# Main.net
KiCad netlist of a schematic drawn in Altium Designer
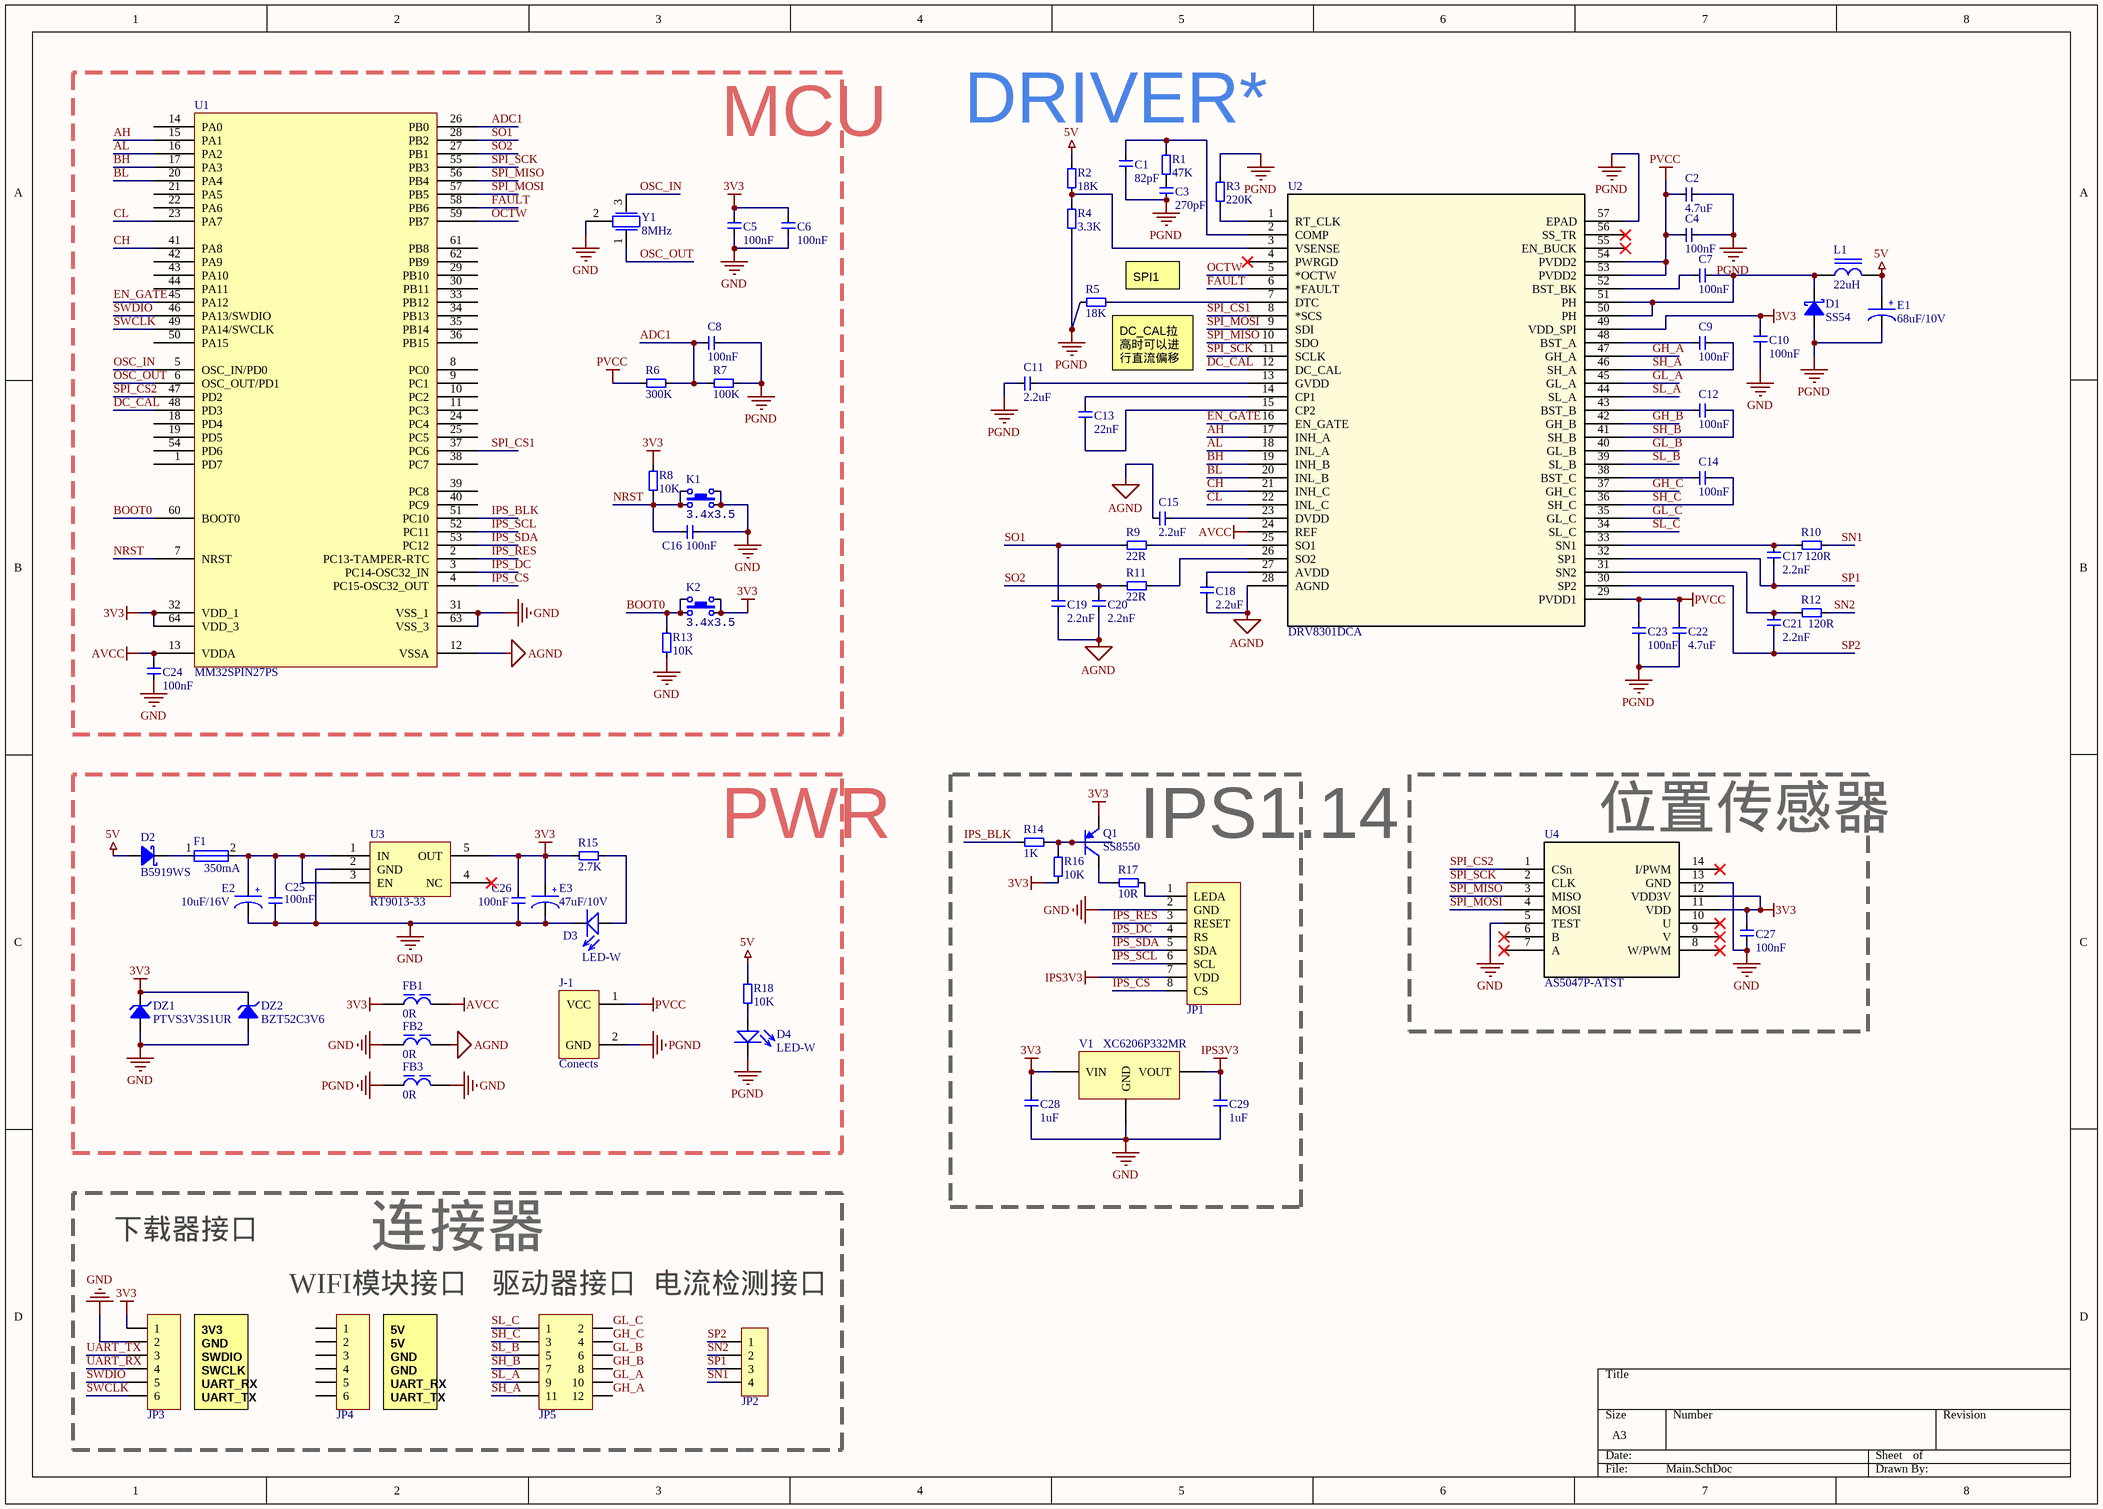
[diagram p0: Main.SchDoc]

(export (version "E")
  (design (tool "Eeschema 10.0.6"))
  (components
    (comp (ref "C1")
      (value "82pF")
      (footprint "C0402_L")
      (description "电容 ¦ 陶瓷电容")
      (fields (field (name "版权归属") "源创客"))
      (libsource (lib "total_lib") (part "C"))
    )
    (comp (ref "C2")
      (value "4.7uF")
      (footprint "C0603_L")
      (description "电容 ¦ 陶瓷电容")
      (fields (field (name "版权归属") "源创客"))
      (libsource (lib "total_lib") (part "C"))
    )
    (comp (ref "C3")
      (value "270pF")
      (footprint "C0402_L")
      (description "电容 ¦ 陶瓷电容")
      (fields (field (name "版权归属") "源创客"))
      (libsource (lib "total_lib") (part "C"))
    )
    (comp (ref "C4")
      (value "100nF")
      (footprint "C0402_L")
      (description "电容 ¦ 陶瓷电容")
      (fields (field (name "版权归属") "源创客"))
      (libsource (lib "total_lib") (part "C"))
    )
    (comp (ref "C5")
      (value "100nF")
      (footprint "C0402_L")
      (description "电容 ¦ 陶瓷电容")
      (fields (field (name "版权归属") "源创客"))
      (libsource (lib "total_lib") (part "C"))
    )
    (comp (ref "C6")
      (value "100nF")
      (footprint "C0402_L")
      (description "电容 ¦ 陶瓷电容")
      (fields (field (name "版权归属") "源创客"))
      (libsource (lib "total_lib") (part "C"))
    )
    (comp (ref "C7")
      (value "100nF")
      (footprint "C0402_L")
      (description "电容 ¦ 陶瓷电容")
      (fields (field (name "版权归属") "源创客"))
      (libsource (lib "total_lib") (part "C"))
    )
    (comp (ref "C8")
      (value "100nF")
      (footprint "C0402_L")
      (description "电容 ¦ 陶瓷电容")
      (fields (field (name "版权归属") "源创客"))
      (libsource (lib "total_lib") (part "C"))
    )
    (comp (ref "C9")
      (value "100nF")
      (footprint "C0402_L")
      (description "电容 ¦ 陶瓷电容")
      (fields (field (name "版权归属") "源创客"))
      (libsource (lib "total_lib") (part "C"))
    )
    (comp (ref "C10")
      (value "100nF")
      (footprint "C0402_L")
      (description "电容 ¦ 陶瓷电容")
      (fields (field (name "版权归属") "源创客"))
      (libsource (lib "total_lib") (part "C"))
    )
    (comp (ref "C11")
      (value "2.2uF")
      (footprint "C0402_L")
      (description "电容 ¦ 陶瓷电容")
      (fields (field (name "版权归属") "源创客"))
      (libsource (lib "total_lib") (part "C"))
    )
    (comp (ref "C12")
      (value "100nF")
      (footprint "C0402_L")
      (description "电容 ¦ 陶瓷电容")
      (fields (field (name "版权归属") "源创客"))
      (libsource (lib "total_lib") (part "C"))
    )
    (comp (ref "C13")
      (value "22nF")
      (footprint "C0402_L")
      (description "电容 ¦ 陶瓷电容")
      (fields (field (name "版权归属") "源创客"))
      (libsource (lib "total_lib") (part "C"))
    )
    (comp (ref "C14")
      (value "100nF")
      (footprint "C0402_L")
      (description "电容 ¦ 陶瓷电容")
      (fields (field (name "版权归属") "源创客"))
      (libsource (lib "total_lib") (part "C"))
    )
    (comp (ref "C15")
      (value "2.2uF")
      (footprint "C0402_L")
      (description "电容 ¦ 陶瓷电容")
      (fields (field (name "版权归属") "源创客"))
      (libsource (lib "total_lib") (part "C"))
    )
    (comp (ref "C16")
      (value "100nF")
      (footprint "C0402_L")
      (description "电容 ¦ 陶瓷电容")
      (fields (field (name "版权归属") "源创客"))
      (libsource (lib "total_lib") (part "C"))
    )
    (comp (ref "C17")
      (value "2.2nF")
      (footprint "C0402_L")
      (description "电容 ¦ 陶瓷电容")
      (fields (field (name "版权归属") "源创客"))
      (libsource (lib "total_lib") (part "C"))
    )
    (comp (ref "C18")
      (value "2.2uF")
      (footprint "C0402_L")
      (description "电容 ¦ 陶瓷电容")
      (fields (field (name "版权归属") "源创客"))
      (libsource (lib "total_lib") (part "C"))
    )
    (comp (ref "C19")
      (value "2.2nF")
      (footprint "C0402_L")
      (description "电容 ¦ 陶瓷电容")
      (fields (field (name "版权归属") "源创客"))
      (libsource (lib "total_lib") (part "C"))
    )
    (comp (ref "C20")
      (value "2.2nF")
      (footprint "C0402_L")
      (description "电容 ¦ 陶瓷电容")
      (fields (field (name "版权归属") "源创客"))
      (libsource (lib "total_lib") (part "C"))
    )
    (comp (ref "C21")
      (value "2.2nF")
      (footprint "C0402_L")
      (description "电容 ¦ 陶瓷电容")
      (fields (field (name "版权归属") "源创客"))
      (libsource (lib "total_lib") (part "C"))
    )
    (comp (ref "C22")
      (value "4.7uF")
      (footprint "C0603_L")
      (description "电容 ¦ 陶瓷电容")
      (fields (field (name "版权归属") "源创客"))
      (libsource (lib "total_lib") (part "C"))
    )
    (comp (ref "C23")
      (value "100nF")
      (footprint "C0402_L")
      (description "电容 ¦ 陶瓷电容")
      (fields (field (name "版权归属") "源创客"))
      (libsource (lib "total_lib") (part "C"))
    )
    (comp (ref "C24")
      (value "100nF")
      (footprint "C0402_L")
      (description "电容 ¦ 陶瓷电容")
      (fields (field (name "版权归属") "源创客"))
      (libsource (lib "total_lib") (part "C"))
    )
    (comp (ref "C25")
      (value "100nF")
      (footprint "C0402_L")
      (description "电容 ¦ 陶瓷电容")
      (fields (field (name "版权归属") "源创客"))
      (libsource (lib "total_lib") (part "C"))
    )
    (comp (ref "C26")
      (value "100nF")
      (footprint "C0402_L")
      (description "电容 ¦ 陶瓷电容")
      (fields (field (name "版权归属") "源创客"))
      (libsource (lib "total_lib") (part "C"))
    )
    (comp (ref "C27")
      (value "100nF")
      (footprint "C0402_L")
      (description "电容 ¦ 陶瓷电容")
      (fields (field (name "版权归属") "源创客"))
      (libsource (lib "total_lib") (part "C"))
    )
    (comp (ref "C28")
      (value "1uF")
      (footprint "C0402_L")
      (description "电容 ¦ 陶瓷电容")
      (fields (field (name "版权归属") "源创客"))
      (libsource (lib "total_lib") (part "C"))
    )
    (comp (ref "C29")
      (value "1uF")
      (footprint "C0402_L")
      (description "电容 ¦ 陶瓷电容")
      (fields (field (name "版权归属") "源创客"))
      (libsource (lib "total_lib") (part "C"))
    )
    (comp (ref "D1")
      (value "SS54")
      (footprint "SMB")
      (description "二极管 ¦ 肖特基二极管")
      (libsource (lib "total_lib") (part "SS54"))
    )
    (comp (ref "D2")
      (value "B5919WS")
      (footprint "SOD-323")
      (description "二极管 ¦ 肖特基二极管")
      (libsource (lib "total_lib") (part "1N5819"))
    )
    (comp (ref "D3")
      (value "LED-W")
      (footprint "LED 0402")
      (description "二极管 ¦ 白色LED")
      (libsource (lib "total_lib") (part "LED-White"))
    )
    (comp (ref "D4")
      (value "LED-W")
      (footprint "LED 0402")
      (description "二极管 ¦ 白色LED")
      (libsource (lib "total_lib") (part "LED-White"))
    )
    (comp (ref "DZ1")
      (value "PTVS3V3S1UR")
      (footprint "SOD-123")
      (description "二极管 ¦ 齐纳二极管")
      (libsource (lib "total_lib") (part "PTVS3V3S1UR"))
    )
    (comp (ref "DZ2")
      (value "BZT52C3V6")
      (footprint "SOD-123")
      (description "二极管 ¦ 齐纳二极管")
      (libsource (lib "total_lib") (part "BZT52C3V6"))
    )
    (comp (ref "E1")
      (value "68uF/10V")
      (footprint "CE D(6.3*5.4)")
      (description "电容 ¦ 电解电容")
      (fields (field (name "版权归属") "源创客"))
      (libsource (lib "total_lib") (part "C-CM"))
    )
    (comp (ref "E2")
      (value "10uF/16V")
      (footprint "C_3528")
      (description "电容 ¦ 钽电容")
      (fields (field (name "版权归属") "源创客"))
      (libsource (lib "total_lib") (part "C-CD"))
    )
    (comp (ref "E3")
      (value "47uF/10V")
      (footprint "C_3528")
      (description "电容 ¦ 钽电容")
      (fields (field (name "版权归属") "源创客"))
      (libsource (lib "total_lib") (part "C-CD"))
    )
    (comp (ref "F1")
      (value "350mA")
      (footprint "R0805_L")
      (description "可复位保险丝")
      (libsource (lib "total_lib") (part "FUSE"))
    )
    (comp (ref "FB1")
      (value "0R")
      (footprint "R0603_L")
      (description "磁珠")
      (libsource (lib "total_lib") (part "FB"))
    )
    (comp (ref "FB2")
      (value "0R")
      (footprint "R0603_L")
      (description "磁珠")
      (libsource (lib "total_lib") (part "FB"))
    )
    (comp (ref "FB3")
      (value "0R")
      (footprint "R1206_L")
      (description "磁珠")
      (libsource (lib "total_lib") (part "FB"))
    )
    (comp (ref "J-1")
      (value "Conects")
      (footprint "connecter-PWR")
      (description "插接件 ¦ 电源接口")
      (fields (field (name "版权归属") "源创客"))
      (libsource (lib "total_lib") (part "Conects"))
    )
    (comp (ref "JP1")
      (value "IPS1.14")
      (footprint "IPS1.14 FPC0.5 2H-WS-8P")
      (description "显示屏 ¦ 1.14寸液晶显示屏")
      (fields (field (name "版权归属") "源创客"))
      (libsource (lib "total_lib") (part "IPS1.14"))
    )
    (comp (ref "JP2")
      (value "HDR-1X4")
      (footprint "connecter-stamps-4p")
      (description "插接件 ¦ 4P接插件")
      (libsource (lib "total_lib") (part "Header 4"))
    )
    (comp (ref "JP3")
      (value "CON-6P")
      (footprint "SH1.0-6P")
      (description "插接件 ¦ SH系列")
      (libsource (lib "total_lib") (part "SH1.0-6P"))
    )
    (comp (ref "JP4")
      (value "CON-6P")
      (footprint "SH1.0-6P")
      (description "插接件 ¦ SH系列")
      (libsource (lib "total_lib") (part "SH1.0-6P"))
    )
    (comp (ref "JP5")
      (value "Header 6X2")
      (footprint "connecter-stamps-12p")
      (description "插接件 ¦ 6*2P接插件")
      (libsource (lib "total_lib") (part "Header  6X2"))
    )
    (comp (ref "K1")
      (value "3.4x3.5")
      (footprint "ButtonTACT_3.5*3.55_90")
      (description "轻触开关 ¦ 3.4x3.5四脚")
      (fields (field (name "Comment") "TACT 4P"))
      (libsource (lib "total_lib") (part "ButtonTACT"))
    )
    (comp (ref "K2")
      (value "3.4x3.5")
      (footprint "ButtonTACT_3.5*3.55_90")
      (description "轻触开关 ¦ 3.4x3.5四脚")
      (fields (field (name "Comment") "TACT 4P"))
      (libsource (lib "total_lib") (part "ButtonTACT"))
    )
    (comp (ref "L1")
      (value "22uH")
      (footprint "NR5040")
      (description "电感 ¦ 贴片功率电感")
      (fields (field (name "版权归属") "源创客"))
      (libsource (lib "total_lib") (part "L-CD"))
    )
    (comp (ref "Q1")
      (value "SS8550")
      (footprint "SOT23")
      (description "三极管 ¦ 高频放大-PNP型")
      (fields (field (name "版权归属") "源创客"))
      (libsource (lib "total_lib") (part "8550-DIP"))
    )
    (comp (ref "R1")
      (value "47K")
      (footprint "R0402_L")
      (description "电阻 ¦ 贴片电阻")
      (fields (field (name "版权归属") "源创客"))
      (libsource (lib "total_lib") (part "R"))
    )
    (comp (ref "R2")
      (value "18K")
      (footprint "R0402_L")
      (description "电阻 ¦ 贴片电阻")
      (fields (field (name "版权归属") "源创客"))
      (libsource (lib "total_lib") (part "R"))
    )
    (comp (ref "R3")
      (value "220K")
      (footprint "R0402_L")
      (description "电阻 ¦ 贴片电阻")
      (fields (field (name "版权归属") "源创客"))
      (libsource (lib "total_lib") (part "R"))
    )
    (comp (ref "R4")
      (value "3.3K")
      (footprint "R0402_L")
      (description "电阻 ¦ 贴片电阻")
      (fields (field (name "版权归属") "源创客"))
      (libsource (lib "total_lib") (part "R"))
    )
    (comp (ref "R5")
      (value "18K")
      (footprint "R0402_L")
      (description "电阻 ¦ 贴片电阻")
      (fields (field (name "版权归属") "源创客"))
      (libsource (lib "total_lib") (part "R"))
    )
    (comp (ref "R6")
      (value "300K")
      (footprint "R0402_L")
      (description "电阻 ¦ 贴片电阻")
      (fields (field (name "版权归属") "源创客"))
      (libsource (lib "total_lib") (part "R"))
    )
    (comp (ref "R7")
      (value "100K")
      (footprint "R0402_L")
      (description "电阻 ¦ 贴片电阻")
      (fields (field (name "版权归属") "源创客"))
      (libsource (lib "total_lib") (part "R"))
    )
    (comp (ref "R8")
      (value "10K")
      (footprint "R0402_L")
      (description "电阻 ¦ 贴片电阻")
      (fields (field (name "版权归属") "源创客"))
      (libsource (lib "total_lib") (part "R"))
    )
    (comp (ref "R9")
      (value "22R")
      (footprint "R0402_L")
      (description "电阻 ¦ 贴片电阻")
      (fields (field (name "版权归属") "源创客"))
      (libsource (lib "total_lib") (part "R"))
    )
    (comp (ref "R10")
      (value "120R")
      (footprint "R0402_L")
      (description "电阻 ¦ 贴片电阻")
      (fields (field (name "版权归属") "源创客"))
      (libsource (lib "total_lib") (part "R"))
    )
    (comp (ref "R11")
      (value "22R")
      (footprint "R0402_L")
      (description "电阻 ¦ 贴片电阻")
      (fields (field (name "版权归属") "源创客"))
      (libsource (lib "total_lib") (part "R"))
    )
    (comp (ref "R12")
      (value "120R")
      (footprint "R0402_L")
      (description "电阻 ¦ 贴片电阻")
      (fields (field (name "版权归属") "源创客"))
      (libsource (lib "total_lib") (part "R"))
    )
    (comp (ref "R13")
      (value "10K")
      (footprint "R0402_L")
      (description "电阻 ¦ 贴片电阻")
      (fields (field (name "版权归属") "源创客"))
      (libsource (lib "total_lib") (part "R"))
    )
    (comp (ref "R14")
      (value "1K")
      (footprint "R0402_L")
      (description "电阻 ¦ 贴片电阻")
      (fields (field (name "版权归属") "源创客"))
      (libsource (lib "total_lib") (part "R"))
    )
    (comp (ref "R15")
      (value "2.7K")
      (footprint "R0402_L")
      (description "电阻 ¦ 贴片电阻")
      (fields (field (name "版权归属") "源创客"))
      (libsource (lib "total_lib") (part "R"))
    )
    (comp (ref "R16")
      (value "10K")
      (footprint "R0402_L")
      (description "电阻 ¦ 贴片电阻")
      (fields (field (name "版权归属") "源创客"))
      (libsource (lib "total_lib") (part "R"))
    )
    (comp (ref "R17")
      (value "10R")
      (footprint "R0402_L")
      (description "电阻 ¦ 贴片电阻")
      (fields (field (name "版权归属") "源创客"))
      (libsource (lib "total_lib") (part "R"))
    )
    (comp (ref "R18")
      (value "10K")
      (footprint "R0402_L")
      (description "电阻 ¦ 贴片电阻")
      (fields (field (name "版权归属") "源创客"))
      (libsource (lib "total_lib") (part "R"))
    )
    (comp (ref "U1")
      (value "MM32SPIN27PS")
      (footprint "LQFP64 10x10_L")
      (description "MCU")
      (libsource (lib "total_lib") (part "MM32SPIN27PS"))
    )
    (comp (ref "U2")
      (value "DRV8301DCA")
      (footprint "DCA56_6P35X3P61")
      (description "No Description Available")
      (fields (field (name "COPYRIGHT") "Copyright (C) 2021 Ultra Librarian. All rights reserved."))
      (libsource (lib "total_lib") (part "DRV8301DCA"))
    )
    (comp (ref "U3")
      (value "RT9013-33")
      (footprint "SOT23-5")
      (description "IC ¦ 低压线性稳压器")
      (libsource (lib "total_lib") (part "RT9013-33"))
    )
    (comp (ref "U4")
      (value "AS5047P-ATST")
      (footprint "TSSOP-14_AMS-L")
      (description "No Description Available")
      (fields (field (name "COPYRIGHT") "Copyright (C) 2022 Ultra Librarian. All rights reserved."))
      (libsource (lib "total_lib") (part "AS5047P-ATST"))
    )
    (comp (ref "V1")
      (value "XC6206P332MR")
      (footprint "SOT23")
      (description "IC ¦ 低压线性稳压芯片")
      (fields (field (name "版权归属") "源创客"))
      (libsource (lib "total_lib") (part "XC6206P332MR"))
    )
    (comp (ref "Y1")
      (value "8MHz")
      (footprint "晶振-3P")
      (description "晶振 ¦ 村田贴片")
      (libsource (lib "total_lib") (part "晶振-3Pin"))
    )
  )
  (nets
    (net (code "1") (name "/ADC1") (class "Default")
      (node (ref "C8") (pin "2") (pinfunction "2_2") (pintype "passive"))
      (node (ref "R6") (pin "2") (pinfunction "2_2") (pintype "passive"))
      (node (ref "R7") (pin "1") (pinfunction "1_1") (pintype "passive"))
      (node (ref "U1") (pin "26") (pinfunction "PB0_26") (pintype "passive"))
    )
    (net (code "2") (name "/AH") (class "Default")
      (node (ref "U1") (pin "15") (pinfunction "PA1_15") (pintype "passive"))
      (node (ref "U2") (pin "17") (pinfunction "INH_A_17") (pintype "passive"))
    )
    (net (code "3") (name "/AL") (class "Default")
      (node (ref "U1") (pin "16") (pinfunction "PA2_16") (pintype "passive"))
      (node (ref "U2") (pin "18") (pinfunction "INL_A_18") (pintype "passive"))
    )
    (net (code "4") (name "/BH") (class "Default")
      (node (ref "U1") (pin "17") (pinfunction "PA3_17") (pintype "passive"))
      (node (ref "U2") (pin "19") (pinfunction "INH_B_19") (pintype "passive"))
    )
    (net (code "5") (name "/BL") (class "Default")
      (node (ref "U1") (pin "20") (pinfunction "PA4_20") (pintype "passive"))
      (node (ref "U2") (pin "20") (pinfunction "INL_B_20") (pintype "passive"))
    )
    (net (code "6") (name "/BOOT0") (class "Default")
      (node (ref "K2") (pin "1") (pinfunction "1_1") (pintype "passive"))
      (node (ref "K2") (pin "3") (pinfunction "3_3") (pintype "passive"))
      (node (ref "R13") (pin "1") (pinfunction "1_1") (pintype "passive"))
      (node (ref "U1") (pin "60") (pinfunction "BOOT0_60") (pintype "passive"))
    )
    (net (code "7") (name "/CH") (class "Default")
      (node (ref "U1") (pin "41") (pinfunction "PA8_41") (pintype "passive"))
      (node (ref "U2") (pin "21") (pinfunction "INH_C_21") (pintype "passive"))
    )
    (net (code "8") (name "/CL") (class "Default")
      (node (ref "U1") (pin "23") (pinfunction "PA7_23") (pintype "passive"))
      (node (ref "U2") (pin "22") (pinfunction "INL_C_22") (pintype "passive"))
    )
    (net (code "9") (name "/DC_CAL") (class "Default")
      (node (ref "U1") (pin "48") (pinfunction "PD3_48") (pintype "passive"))
      (node (ref "U2") (pin "12") (pinfunction "DC_CAL_12") (pintype "passive"))
    )
    (net (code "10") (name "/EN_GATE") (class "Default")
      (node (ref "U1") (pin "45") (pinfunction "PA12_45") (pintype "passive"))
      (node (ref "U2") (pin "16") (pinfunction "EN_GATE_16") (pintype "passive"))
    )
    (net (code "11") (name "/FAULT") (class "Default")
      (node (ref "U1") (pin "58") (pinfunction "PB6_58") (pintype "passive"))
      (node (ref "U2") (pin "6") (pinfunction "*FAULT_6") (pintype "passive"))
    )
    (net (code "12") (name "/GH_A") (class "Default")
      (node (ref "JP5") (pin "12") (pinfunction "12_12") (pintype "passive"))
      (node (ref "U2") (pin "47") (pinfunction "GH_A_47") (pintype "passive"))
    )
    (net (code "13") (name "/GH_B") (class "Default")
      (node (ref "JP5") (pin "8") (pinfunction "8_8") (pintype "passive"))
      (node (ref "U2") (pin "42") (pinfunction "GH_B_42") (pintype "passive"))
    )
    (net (code "14") (name "/GH_C") (class "Default")
      (node (ref "JP5") (pin "4") (pinfunction "4_4") (pintype "passive"))
      (node (ref "U2") (pin "37") (pinfunction "GH_C_37") (pintype "passive"))
    )
    (net (code "15") (name "/GL_A") (class "Default")
      (node (ref "JP5") (pin "10") (pinfunction "10_10") (pintype "passive"))
      (node (ref "U2") (pin "45") (pinfunction "GL_A_45") (pintype "passive"))
    )
    (net (code "16") (name "/GL_B") (class "Default")
      (node (ref "JP5") (pin "6") (pinfunction "6_6") (pintype "passive"))
      (node (ref "U2") (pin "40") (pinfunction "GL_B_40") (pintype "passive"))
    )
    (net (code "17") (name "/GL_C") (class "Default")
      (node (ref "JP5") (pin "2") (pinfunction "2_2") (pintype "passive"))
      (node (ref "U2") (pin "35") (pinfunction "GL_C_35") (pintype "passive"))
    )
    (net (code "18") (name "/IPS_BLK") (class "Default")
      (node (ref "R14") (pin "1") (pinfunction "1_1") (pintype "passive"))
      (node (ref "U1") (pin "51") (pinfunction "PC10_51") (pintype "passive"))
    )
    (net (code "19") (name "/IPS_CS") (class "Default")
      (node (ref "JP1") (pin "8") (pinfunction "CS_8") (pintype "passive"))
      (node (ref "U1") (pin "4") (pinfunction "PC15-OSC32_OUT_4") (pintype "passive"))
    )
    (net (code "20") (name "/IPS_DC") (class "Default")
      (node (ref "JP1") (pin "4") (pinfunction "RS_4") (pintype "passive"))
      (node (ref "U1") (pin "3") (pinfunction "PC14-OSC32_IN_3") (pintype "passive"))
    )
    (net (code "21") (name "/IPS_RES") (class "Default")
      (node (ref "JP1") (pin "3") (pinfunction "RESET_3") (pintype "passive"))
      (node (ref "U1") (pin "2") (pinfunction "PC13-TAMPER-RTC_2") (pintype "passive"))
    )
    (net (code "22") (name "/IPS_SCL") (class "Default")
      (node (ref "JP1") (pin "6") (pinfunction "SCL_6") (pintype "passive"))
      (node (ref "U1") (pin "52") (pinfunction "PC11_52") (pintype "passive"))
    )
    (net (code "23") (name "/IPS_SDA") (class "Default")
      (node (ref "JP1") (pin "5") (pinfunction "SDA_5") (pintype "passive"))
      (node (ref "U1") (pin "53") (pinfunction "PC12_53") (pintype "passive"))
    )
    (net (code "24") (name "/NRST") (class "Default")
      (node (ref "C16") (pin "1") (pinfunction "1_1") (pintype "passive"))
      (node (ref "K1") (pin "1") (pinfunction "1_1") (pintype "passive"))
      (node (ref "K1") (pin "3") (pinfunction "3_3") (pintype "passive"))
      (node (ref "R8") (pin "2") (pinfunction "2_2") (pintype "passive"))
      (node (ref "U1") (pin "7") (pinfunction "NRST_7") (pintype "passive"))
    )
    (net (code "25") (name "/OCTW") (class "Default")
      (node (ref "U1") (pin "59") (pinfunction "PB7_59") (pintype "passive"))
      (node (ref "U2") (pin "5") (pinfunction "*OCTW_5") (pintype "passive"))
    )
    (net (code "26") (name "/OSC_IN") (class "Default")
      (node (ref "U1") (pin "5") (pinfunction "OSC_IN/PD0_5") (pintype "passive"))
      (node (ref "Y1") (pin "3") (pinfunction "3_3") (pintype "passive"))
    )
    (net (code "27") (name "/OSC_OUT") (class "Default")
      (node (ref "U1") (pin "6") (pinfunction "OSC_OUT/PD1_6") (pintype "passive"))
      (node (ref "Y1") (pin "1") (pinfunction "1_1") (pintype "passive"))
    )
    (net (code "28") (name "/SH_A") (class "Default")
      (node (ref "C9") (pin "1") (pinfunction "1_1") (pintype "passive"))
      (node (ref "JP5") (pin "11") (pinfunction "11_11") (pintype "passive"))
      (node (ref "U2") (pin "46") (pinfunction "SH_A_46") (pintype "passive"))
    )
    (net (code "29") (name "/SH_B") (class "Default")
      (node (ref "C12") (pin "1") (pinfunction "1_1") (pintype "passive"))
      (node (ref "JP5") (pin "7") (pinfunction "7_7") (pintype "passive"))
      (node (ref "U2") (pin "41") (pinfunction "SH_B_41") (pintype "passive"))
    )
    (net (code "30") (name "/SH_C") (class "Default")
      (node (ref "C14") (pin "1") (pinfunction "1_1") (pintype "passive"))
      (node (ref "JP5") (pin "3") (pinfunction "3_3") (pintype "passive"))
      (node (ref "U2") (pin "36") (pinfunction "SH_C_36") (pintype "passive"))
    )
    (net (code "31") (name "/SL_A") (class "Default")
      (node (ref "JP5") (pin "9") (pinfunction "9_9") (pintype "passive"))
      (node (ref "U2") (pin "44") (pinfunction "SL_A_44") (pintype "passive"))
    )
    (net (code "32") (name "/SL_B") (class "Default")
      (node (ref "JP5") (pin "5") (pinfunction "5_5") (pintype "passive"))
      (node (ref "U2") (pin "39") (pinfunction "SL_B_39") (pintype "passive"))
    )
    (net (code "33") (name "/SL_C") (class "Default")
      (node (ref "JP5") (pin "1") (pinfunction "1_1") (pintype "passive"))
      (node (ref "U2") (pin "34") (pinfunction "SL_C_34") (pintype "passive"))
    )
    (net (code "34") (name "/SN1") (class "Default")
      (node (ref "JP2") (pin "4") (pinfunction "4_4") (pintype "passive"))
      (node (ref "R10") (pin "1") (pinfunction "1_1") (pintype "passive"))
    )
    (net (code "35") (name "/SN2") (class "Default")
      (node (ref "JP2") (pin "2") (pinfunction "2_2") (pintype "passive"))
      (node (ref "R12") (pin "1") (pinfunction "1_1") (pintype "passive"))
    )
    (net (code "36") (name "/SO1") (class "Default")
      (node (ref "C19") (pin "2") (pinfunction "2_2") (pintype "passive"))
      (node (ref "R9") (pin "2") (pinfunction "2_2") (pintype "passive"))
      (node (ref "U1") (pin "28") (pinfunction "PB2_28") (pintype "passive"))
    )
    (net (code "37") (name "/SO2") (class "Default")
      (node (ref "C20") (pin "2") (pinfunction "2_2") (pintype "passive"))
      (node (ref "R11") (pin "2") (pinfunction "2_2") (pintype "passive"))
      (node (ref "U1") (pin "27") (pinfunction "PB1_27") (pintype "passive"))
    )
    (net (code "38") (name "/SP1") (class "Default")
      (node (ref "C17") (pin "1") (pinfunction "1_1") (pintype "passive"))
      (node (ref "JP2") (pin "3") (pinfunction "3_3") (pintype "passive"))
      (node (ref "U2") (pin "32") (pinfunction "SP1_32") (pintype "passive"))
    )
    (net (code "39") (name "/SP2") (class "Default")
      (node (ref "C21") (pin "1") (pinfunction "1_1") (pintype "passive"))
      (node (ref "JP2") (pin "1") (pinfunction "1_1") (pintype "passive"))
      (node (ref "U2") (pin "30") (pinfunction "SP2_30") (pintype "passive"))
    )
    (net (code "40") (name "/SPI_CS1") (class "Default")
      (node (ref "U1") (pin "37") (pinfunction "PC6_37") (pintype "passive"))
      (node (ref "U2") (pin "8") (pinfunction "*SCS_8") (pintype "passive"))
    )
    (net (code "41") (name "/SPI_CS2") (class "Default")
      (node (ref "U1") (pin "47") (pinfunction "PD2_47") (pintype "passive"))
      (node (ref "U4") (pin "1") (pinfunction "CSn_1") (pintype "passive"))
    )
    (net (code "42") (name "/SPI_MISO") (class "Default")
      (node (ref "U1") (pin "56") (pinfunction "PB4_56") (pintype "passive"))
      (node (ref "U2") (pin "10") (pinfunction "SDO_10") (pintype "passive"))
      (node (ref "U4") (pin "3") (pinfunction "MISO_3") (pintype "passive"))
    )
    (net (code "43") (name "/SPI_MOSI") (class "Default")
      (node (ref "U1") (pin "57") (pinfunction "PB5_57") (pintype "passive"))
      (node (ref "U2") (pin "9") (pinfunction "SDI_9") (pintype "passive"))
      (node (ref "U4") (pin "4") (pinfunction "MOSI_4") (pintype "passive"))
    )
    (net (code "44") (name "/SPI_SCK") (class "Default")
      (node (ref "U1") (pin "55") (pinfunction "PB3_55") (pintype "passive"))
      (node (ref "U2") (pin "11") (pinfunction "SCLK_11") (pintype "passive"))
      (node (ref "U4") (pin "2") (pinfunction "CLK_2") (pintype "passive"))
    )
    (net (code "45") (name "/SWCLK") (class "Default")
      (node (ref "JP3") (pin "6") (pinfunction "6_6") (pintype "passive"))
      (node (ref "U1") (pin "49") (pinfunction "PA14/SWCLK_49") (pintype "passive"))
    )
    (net (code "46") (name "/SWDIO") (class "Default")
      (node (ref "JP3") (pin "5") (pinfunction "5_5") (pintype "passive"))
      (node (ref "U1") (pin "46") (pinfunction "PA13/SWDIO_46") (pintype "passive"))
    )
    (net (code "47") (name "/UART_RX") (class "Default")
      (node (ref "JP3") (pin "4") (pinfunction "4_4") (pintype "passive"))
    )
    (net (code "48") (name "/UART_TX") (class "Default")
      (node (ref "JP3") (pin "3") (pinfunction "3_3") (pintype "passive"))
    )
    (net (code "49") (name "3V3") (class "Default")
      (node (ref "C10") (pin "1") (pinfunction "1_1") (pintype "passive"))
      (node (ref "C26") (pin "1") (pinfunction "1_1") (pintype "passive"))
      (node (ref "C27") (pin "1") (pinfunction "1_1") (pintype "passive"))
      (node (ref "C28") (pin "2") (pinfunction "2_2") (pintype "passive"))
      (node (ref "C5") (pin "2") (pinfunction "2_2") (pintype "passive"))
      (node (ref "C6") (pin "2") (pinfunction "2_2") (pintype "passive"))
      (node (ref "DZ1") (pin "2") (pinfunction "K_2") (pintype "passive"))
      (node (ref "DZ2") (pin "2") (pinfunction "K_2") (pintype "passive"))
      (node (ref "E3") (pin "1") (pinfunction "A_1") (pintype "passive"))
      (node (ref "FB1") (pin "2") (pinfunction "2_2") (pintype "passive"))
      (node (ref "JP3") (pin "1") (pinfunction "1_1") (pintype "passive"))
      (node (ref "K2") (pin "2") (pinfunction "2_2") (pintype "passive"))
      (node (ref "K2") (pin "4") (pinfunction "4_4") (pintype "passive"))
      (node (ref "Q1") (pin "2") (pinfunction "E_2") (pintype "passive"))
      (node (ref "R15") (pin "1") (pinfunction "1_1") (pintype "passive"))
      (node (ref "R16") (pin "1") (pinfunction "1_1") (pintype "passive"))
      (node (ref "R8") (pin "1") (pinfunction "1_1") (pintype "passive"))
      (node (ref "U1") (pin "32") (pinfunction "VDD_1_32") (pintype "passive"))
      (node (ref "U1") (pin "64") (pinfunction "VDD_3_64") (pintype "passive"))
      (node (ref "U2") (pin "49") (pinfunction "VDD_SPI_49") (pintype "passive"))
      (node (ref "U3") (pin "5") (pinfunction "OUT_5") (pintype "passive"))
      (node (ref "U4") (pin "11") (pinfunction "VDD_11") (pintype "passive"))
      (node (ref "U4") (pin "12") (pinfunction "VDD3V_12") (pintype "passive"))
      (node (ref "V1") (pin "3") (pinfunction "VIN_3") (pintype "passive"))
    )
    (net (code "50") (name "5V") (class "Default")
      (node (ref "D2") (pin "1") (pinfunction "A_1") (pintype "passive"))
      (node (ref "E1") (pin "1") (pinfunction "A_1") (pintype "passive"))
      (node (ref "L1") (pin "2") (pinfunction "2_2") (pintype "passive"))
      (node (ref "R18") (pin "1") (pinfunction "1_1") (pintype "passive"))
      (node (ref "R2") (pin "2") (pinfunction "2_2") (pintype "passive"))
    )
    (net (code "51") (name "AGND") (class "Default")
      (node (ref "C15") (pin "1") (pinfunction "1_1") (pintype "passive"))
      (node (ref "C18") (pin "1") (pinfunction "1_1") (pintype "passive"))
      (node (ref "C19") (pin "1") (pinfunction "1_1") (pintype "passive"))
      (node (ref "C20") (pin "1") (pinfunction "1_1") (pintype "passive"))
      (node (ref "FB2") (pin "1") (pinfunction "1_1") (pintype "passive"))
      (node (ref "U1") (pin "12") (pinfunction "VSSA_12") (pintype "passive"))
      (node (ref "U2") (pin "28") (pinfunction "AGND_28") (pintype "passive"))
    )
    (net (code "52") (name "AVCC") (class "Default")
      (node (ref "C24") (pin "2") (pinfunction "2_2") (pintype "passive"))
      (node (ref "FB1") (pin "1") (pinfunction "1_1") (pintype "passive"))
      (node (ref "U1") (pin "13") (pinfunction "VDDA_13") (pintype "passive"))
      (node (ref "U2") (pin "24") (pinfunction "REF_24") (pintype "passive"))
    )
    (net (code "53") (name "GND") (class "Default")
      (node (ref "C10") (pin "2") (pinfunction "2_2") (pintype "passive"))
      (node (ref "C16") (pin "2") (pinfunction "2_2") (pintype "passive"))
      (node (ref "C24") (pin "1") (pinfunction "1_1") (pintype "passive"))
      (node (ref "C25") (pin "2") (pinfunction "2_2") (pintype "passive"))
      (node (ref "C26") (pin "2") (pinfunction "2_2") (pintype "passive"))
      (node (ref "C27") (pin "2") (pinfunction "2_2") (pintype "passive"))
      (node (ref "C28") (pin "1") (pinfunction "1_1") (pintype "passive"))
      (node (ref "C29") (pin "1") (pinfunction "1_1") (pintype "passive"))
      (node (ref "C5") (pin "1") (pinfunction "1_1") (pintype "passive"))
      (node (ref "C6") (pin "1") (pinfunction "1_1") (pintype "passive"))
      (node (ref "D3") (pin "2") (pinfunction "1_2") (pintype "passive"))
      (node (ref "DZ1") (pin "1") (pinfunction "A_1") (pintype "passive"))
      (node (ref "DZ2") (pin "1") (pinfunction "A_1") (pintype "passive"))
      (node (ref "E2") (pin "2") (pinfunction "K_2") (pintype "passive"))
      (node (ref "E3") (pin "2") (pinfunction "K_2") (pintype "passive"))
      (node (ref "FB2") (pin "2") (pinfunction "2_2") (pintype "passive"))
      (node (ref "FB3") (pin "1") (pinfunction "1_1") (pintype "passive"))
      (node (ref "JP1") (pin "2") (pinfunction "GND_2") (pintype "passive"))
      (node (ref "JP3") (pin "2") (pinfunction "2_2") (pintype "passive"))
      (node (ref "K1") (pin "2") (pinfunction "2_2") (pintype "passive"))
      (node (ref "K1") (pin "4") (pinfunction "4_4") (pintype "passive"))
      (node (ref "R13") (pin "2") (pinfunction "2_2") (pintype "passive"))
      (node (ref "U1") (pin "31") (pinfunction "VSS_1_31") (pintype "passive"))
      (node (ref "U1") (pin "63") (pinfunction "VSS_3_63") (pintype "passive"))
      (node (ref "U3") (pin "2") (pinfunction "GND_2") (pintype "passive"))
      (node (ref "U4") (pin "13") (pinfunction "GND_13") (pintype "passive"))
      (node (ref "U4") (pin "5") (pinfunction "TEST_5") (pintype "passive"))
      (node (ref "V1") (pin "1") (pinfunction "GND_1") (pintype "passive"))
      (node (ref "Y1") (pin "2") (pinfunction "2_2") (pintype "passive"))
    )
    (net (code "54") (name "IPS3V3") (class "Default")
      (node (ref "C29") (pin "2") (pinfunction "2_2") (pintype "passive"))
      (node (ref "JP1") (pin "7") (pinfunction "VDD_7") (pintype "passive"))
      (node (ref "V1") (pin "2") (pinfunction "VOUT_2") (pintype "passive"))
    )
    (net (code "55") (name "Net-(C3-Pad2)") (class "Default")
      (node (ref "C3") (pin "2") (pinfunction "2_2") (pintype "passive"))
      (node (ref "R1") (pin "1") (pinfunction "1_1") (pintype "passive"))
    )
    (net (code "56") (name "Net-(D1-K)") (class "Default")
      (node (ref "C7") (pin "1") (pinfunction "1_1") (pintype "passive"))
      (node (ref "D1") (pin "2") (pinfunction "K_2") (pintype "passive"))
      (node (ref "L1") (pin "1") (pinfunction "1_1") (pintype "passive"))
      (node (ref "U2") (pin "50") (pinfunction "PH_50") (pintype "passive"))
      (node (ref "U2") (pin "51") (pinfunction "PH_51") (pintype "passive"))
    )
    (net (code "57") (name "Net-(D2-K)") (class "Default")
      (node (ref "D2") (pin "2") (pinfunction "K_2") (pintype "passive"))
      (node (ref "F1") (pin "1") (pinfunction "116_1") (pintype "passive"))
    )
    (net (code "58") (name "Net-(D3-2)") (class "Default")
      (node (ref "D3") (pin "1") (pinfunction "2_1") (pintype "passive"))
      (node (ref "R15") (pin "2") (pinfunction "2_2") (pintype "passive"))
    )
    (net (code "59") (name "Net-(D4-2)") (class "Default")
      (node (ref "D4") (pin "1") (pinfunction "2_1") (pintype "passive"))
      (node (ref "R18") (pin "2") (pinfunction "2_2") (pintype "passive"))
    )
    (net (code "60") (name "Net-(E2-A)") (class "Default")
      (node (ref "C25") (pin "1") (pinfunction "1_1") (pintype "passive"))
      (node (ref "E2") (pin "1") (pinfunction "A_1") (pintype "passive"))
      (node (ref "F1") (pin "2") (pinfunction "2_2") (pintype "passive"))
      (node (ref "U3") (pin "1") (pinfunction "IN_1") (pintype "passive"))
      (node (ref "U3") (pin "3") (pinfunction "EN_3") (pintype "passive"))
    )
    (net (code "61") (name "Net-(JP1-LEDA)") (class "Default")
      (node (ref "JP1") (pin "1") (pinfunction "LEDA_1") (pintype "passive"))
      (node (ref "R17") (pin "2") (pinfunction "2_2") (pintype "passive"))
    )
    (net (code "62") (name "Net-(Q1-B)") (class "Default")
      (node (ref "Q1") (pin "1") (pinfunction "B_1") (pintype "passive"))
      (node (ref "R14") (pin "2") (pinfunction "2_2") (pintype "passive"))
      (node (ref "R16") (pin "2") (pinfunction "2_2") (pintype "passive"))
    )
    (net (code "63") (name "Net-(Q1-C)") (class "Default")
      (node (ref "Q1") (pin "3") (pinfunction "C_3") (pintype "passive"))
      (node (ref "R17") (pin "1") (pinfunction "1_1") (pintype "passive"))
    )
    (net (code "64") (name "Net-(U2-AVDD)") (class "Default")
      (node (ref "C18") (pin "2") (pinfunction "2_2") (pintype "passive"))
      (node (ref "U2") (pin "27") (pinfunction "AVDD_27") (pintype "passive"))
    )
    (net (code "65") (name "Net-(U2-BST_A)") (class "Default")
      (node (ref "C9") (pin "2") (pinfunction "2_2") (pintype "passive"))
      (node (ref "U2") (pin "48") (pinfunction "BST_A_48") (pintype "passive"))
    )
    (net (code "66") (name "Net-(U2-BST_B)") (class "Default")
      (node (ref "C12") (pin "2") (pinfunction "2_2") (pintype "passive"))
      (node (ref "U2") (pin "43") (pinfunction "BST_B_43") (pintype "passive"))
    )
    (net (code "67") (name "Net-(U2-BST_BK)") (class "Default")
      (node (ref "C7") (pin "2") (pinfunction "2_2") (pintype "passive"))
      (node (ref "U2") (pin "52") (pinfunction "BST_BK_52") (pintype "passive"))
    )
    (net (code "68") (name "Net-(U2-BST_C)") (class "Default")
      (node (ref "C14") (pin "2") (pinfunction "2_2") (pintype "passive"))
      (node (ref "U2") (pin "38") (pinfunction "BST_C_38") (pintype "passive"))
    )
    (net (code "69") (name "Net-(U2-COMP)") (class "Default")
      (node (ref "C1") (pin "2") (pinfunction "2_2") (pintype "passive"))
      (node (ref "R1") (pin "2") (pinfunction "2_2") (pintype "passive"))
      (node (ref "U2") (pin "2") (pinfunction "COMP_2") (pintype "passive"))
    )
    (net (code "70") (name "Net-(U2-CP1)") (class "Default")
      (node (ref "C13") (pin "2") (pinfunction "2_2") (pintype "passive"))
      (node (ref "U2") (pin "14") (pinfunction "CP1_14") (pintype "passive"))
    )
    (net (code "71") (name "Net-(U2-CP2)") (class "Default")
      (node (ref "C13") (pin "1") (pinfunction "1_1") (pintype "passive"))
      (node (ref "U2") (pin "15") (pinfunction "CP2_15") (pintype "passive"))
    )
    (net (code "72") (name "Net-(U2-DTC)") (class "Default")
      (node (ref "R5") (pin "1") (pinfunction "1_1") (pintype "passive"))
      (node (ref "U2") (pin "7") (pinfunction "DTC_7") (pintype "passive"))
    )
    (net (code "73") (name "Net-(U2-DVDD)") (class "Default")
      (node (ref "C15") (pin "2") (pinfunction "2_2") (pintype "passive"))
      (node (ref "U2") (pin "23") (pinfunction "DVDD_23") (pintype "passive"))
    )
    (net (code "74") (name "Net-(U2-GVDD)") (class "Default")
      (node (ref "C11") (pin "2") (pinfunction "2_2") (pintype "passive"))
      (node (ref "U2") (pin "13") (pinfunction "GVDD_13") (pintype "passive"))
    )
    (net (code "75") (name "Net-(U2-RT_CLK)") (class "Default")
      (node (ref "R3") (pin "1") (pinfunction "1_1") (pintype "passive"))
      (node (ref "U2") (pin "1") (pinfunction "RT_CLK_1") (pintype "passive"))
    )
    (net (code "76") (name "Net-(U2-SN1)") (class "Default")
      (node (ref "C17") (pin "2") (pinfunction "2_2") (pintype "passive"))
      (node (ref "R10") (pin "2") (pinfunction "2_2") (pintype "passive"))
      (node (ref "U2") (pin "33") (pinfunction "SN1_33") (pintype "passive"))
    )
    (net (code "77") (name "Net-(U2-SN2)") (class "Default")
      (node (ref "C21") (pin "2") (pinfunction "2_2") (pintype "passive"))
      (node (ref "R12") (pin "2") (pinfunction "2_2") (pintype "passive"))
      (node (ref "U2") (pin "31") (pinfunction "SN2_31") (pintype "passive"))
    )
    (net (code "78") (name "Net-(U2-SO1)") (class "Default")
      (node (ref "R9") (pin "1") (pinfunction "1_1") (pintype "passive"))
      (node (ref "U2") (pin "25") (pinfunction "SO1_25") (pintype "passive"))
    )
    (net (code "79") (name "Net-(U2-SO2)") (class "Default")
      (node (ref "R11") (pin "1") (pinfunction "1_1") (pintype "passive"))
      (node (ref "U2") (pin "26") (pinfunction "SO2_26") (pintype "passive"))
    )
    (net (code "80") (name "Net-(U2-VSENSE)") (class "Default")
      (node (ref "R2") (pin "1") (pinfunction "1_1") (pintype "passive"))
      (node (ref "R4") (pin "2") (pinfunction "2_2") (pintype "passive"))
      (node (ref "U2") (pin "3") (pinfunction "VSENSE_3") (pintype "passive"))
    )
    (net (code "81") (name "PGND") (class "Default")
      (node (ref "C1") (pin "1") (pinfunction "1_1") (pintype "passive"))
      (node (ref "C11") (pin "1") (pinfunction "1_1") (pintype "passive"))
      (node (ref "C2") (pin "2") (pinfunction "2_2") (pintype "passive"))
      (node (ref "C22") (pin "1") (pinfunction "1_1") (pintype "passive"))
      (node (ref "C23") (pin "1") (pinfunction "1_1") (pintype "passive"))
      (node (ref "C3") (pin "1") (pinfunction "1_1") (pintype "passive"))
      (node (ref "C4") (pin "2") (pinfunction "2_2") (pintype "passive"))
      (node (ref "C8") (pin "1") (pinfunction "1_1") (pintype "passive"))
      (node (ref "D1") (pin "1") (pinfunction "A_1") (pintype "passive"))
      (node (ref "D4") (pin "2") (pinfunction "1_2") (pintype "passive"))
      (node (ref "E1") (pin "2") (pinfunction "K_2") (pintype "passive"))
      (node (ref "FB3") (pin "2") (pinfunction "2_2") (pintype "passive"))
      (node (ref "J-1") (pin "2") (pinfunction "GND_2") (pintype "passive"))
      (node (ref "R3") (pin "2") (pinfunction "2_2") (pintype "passive"))
      (node (ref "R4") (pin "1") (pinfunction "1_1") (pintype "passive"))
      (node (ref "R5") (pin "2") (pinfunction "2_2") (pintype "passive"))
      (node (ref "R7") (pin "2") (pinfunction "2_2") (pintype "passive"))
      (node (ref "U2") (pin "57") (pinfunction "EPAD_57") (pintype "passive"))
    )
    (net (code "82") (name "PVCC") (class "Default")
      (node (ref "C2") (pin "1") (pinfunction "1_1") (pintype "passive"))
      (node (ref "C22") (pin "2") (pinfunction "2_2") (pintype "passive"))
      (node (ref "C23") (pin "2") (pinfunction "2_2") (pintype "passive"))
      (node (ref "C4") (pin "1") (pinfunction "1_1") (pintype "passive"))
      (node (ref "J-1") (pin "1") (pinfunction "VCC_1") (pintype "passive"))
      (node (ref "R6") (pin "1") (pinfunction "1_1") (pintype "passive"))
      (node (ref "U2") (pin "29") (pinfunction "PVDD1_29") (pintype "passive"))
      (node (ref "U2") (pin "53") (pinfunction "PVDD2_53") (pintype "passive"))
      (node (ref "U2") (pin "54") (pinfunction "PVDD2_54") (pintype "passive"))
    )
    (net (code "83") (name "unconnected-(JP4-Pad1)") (class "Default")
      (node (ref "JP4") (pin "1") (pinfunction "1_1") (pintype "passive"))
    )
    (net (code "84") (name "unconnected-(JP4-Pad2)") (class "Default")
      (node (ref "JP4") (pin "2") (pinfunction "2_2") (pintype "passive"))
    )
    (net (code "85") (name "unconnected-(JP4-Pad3)") (class "Default")
      (node (ref "JP4") (pin "3") (pinfunction "3_3") (pintype "passive"))
    )
    (net (code "86") (name "unconnected-(JP4-Pad4)") (class "Default")
      (node (ref "JP4") (pin "4") (pinfunction "4_4") (pintype "passive"))
    )
    (net (code "87") (name "unconnected-(JP4-Pad5)") (class "Default")
      (node (ref "JP4") (pin "5") (pinfunction "5_5") (pintype "passive"))
    )
    (net (code "88") (name "unconnected-(JP4-Pad6)") (class "Default")
      (node (ref "JP4") (pin "6") (pinfunction "6_6") (pintype "passive"))
    )
    (net (code "89") (name "unconnected-(U1-PA0-Pad14)") (class "Default")
      (node (ref "U1") (pin "14") (pinfunction "PA0_14") (pintype "passive"))
    )
    (net (code "90") (name "unconnected-(U1-PA5-Pad21)") (class "Default")
      (node (ref "U1") (pin "21") (pinfunction "PA5_21") (pintype "passive"))
    )
    (net (code "91") (name "unconnected-(U1-PA6-Pad22)") (class "Default")
      (node (ref "U1") (pin "22") (pinfunction "PA6_22") (pintype "passive"))
    )
    (net (code "92") (name "unconnected-(U1-PA9-Pad42)") (class "Default")
      (node (ref "U1") (pin "42") (pinfunction "PA9_42") (pintype "passive"))
    )
    (net (code "93") (name "unconnected-(U1-PA10-Pad43)") (class "Default")
      (node (ref "U1") (pin "43") (pinfunction "PA10_43") (pintype "passive"))
    )
    (net (code "94") (name "unconnected-(U1-PA11-Pad44)") (class "Default")
      (node (ref "U1") (pin "44") (pinfunction "PA11_44") (pintype "passive"))
    )
    (net (code "95") (name "unconnected-(U1-PA15-Pad50)") (class "Default")
      (node (ref "U1") (pin "50") (pinfunction "PA15_50") (pintype "passive"))
    )
    (net (code "96") (name "unconnected-(U1-PB8-Pad61)") (class "Default")
      (node (ref "U1") (pin "61") (pinfunction "PB8_61") (pintype "passive"))
    )
    (net (code "97") (name "unconnected-(U1-PB9-Pad62)") (class "Default")
      (node (ref "U1") (pin "62") (pinfunction "PB9_62") (pintype "passive"))
    )
    (net (code "98") (name "unconnected-(U1-PB10-Pad29)") (class "Default")
      (node (ref "U1") (pin "29") (pinfunction "PB10_29") (pintype "passive"))
    )
    (net (code "99") (name "unconnected-(U1-PB11-Pad30)") (class "Default")
      (node (ref "U1") (pin "30") (pinfunction "PB11_30") (pintype "passive"))
    )
    (net (code "100") (name "unconnected-(U1-PB12-Pad33)") (class "Default")
      (node (ref "U1") (pin "33") (pinfunction "PB12_33") (pintype "passive"))
    )
    (net (code "101") (name "unconnected-(U1-PB13-Pad34)") (class "Default")
      (node (ref "U1") (pin "34") (pinfunction "PB13_34") (pintype "passive"))
    )
    (net (code "102") (name "unconnected-(U1-PB14-Pad35)") (class "Default")
      (node (ref "U1") (pin "35") (pinfunction "PB14_35") (pintype "passive"))
    )
    (net (code "103") (name "unconnected-(U1-PB15-Pad36)") (class "Default")
      (node (ref "U1") (pin "36") (pinfunction "PB15_36") (pintype "passive"))
    )
    (net (code "104") (name "unconnected-(U1-PC0-Pad8)") (class "Default")
      (node (ref "U1") (pin "8") (pinfunction "PC0_8") (pintype "passive"))
    )
    (net (code "105") (name "unconnected-(U1-PC1-Pad9)") (class "Default")
      (node (ref "U1") (pin "9") (pinfunction "PC1_9") (pintype "passive"))
    )
    (net (code "106") (name "unconnected-(U1-PC2-Pad10)") (class "Default")
      (node (ref "U1") (pin "10") (pinfunction "PC2_10") (pintype "passive"))
    )
    (net (code "107") (name "unconnected-(U1-PC3-Pad11)") (class "Default")
      (node (ref "U1") (pin "11") (pinfunction "PC3_11") (pintype "passive"))
    )
    (net (code "108") (name "unconnected-(U1-PC4-Pad24)") (class "Default")
      (node (ref "U1") (pin "24") (pinfunction "PC4_24") (pintype "passive"))
    )
    (net (code "109") (name "unconnected-(U1-PC5-Pad25)") (class "Default")
      (node (ref "U1") (pin "25") (pinfunction "PC5_25") (pintype "passive"))
    )
    (net (code "110") (name "unconnected-(U1-PC7-Pad38)") (class "Default")
      (node (ref "U1") (pin "38") (pinfunction "PC7_38") (pintype "passive"))
    )
    (net (code "111") (name "unconnected-(U1-PC8-Pad39)") (class "Default")
      (node (ref "U1") (pin "39") (pinfunction "PC8_39") (pintype "passive"))
    )
    (net (code "112") (name "unconnected-(U1-PC9-Pad40)") (class "Default")
      (node (ref "U1") (pin "40") (pinfunction "PC9_40") (pintype "passive"))
    )
    (net (code "113") (name "unconnected-(U1-PD4-Pad18)") (class "Default")
      (node (ref "U1") (pin "18") (pinfunction "PD4_18") (pintype "passive"))
    )
    (net (code "114") (name "unconnected-(U1-PD5-Pad19)") (class "Default")
      (node (ref "U1") (pin "19") (pinfunction "PD5_19") (pintype "passive"))
    )
    (net (code "115") (name "unconnected-(U1-PD6-Pad54)") (class "Default")
      (node (ref "U1") (pin "54") (pinfunction "PD6_54") (pintype "passive"))
    )
    (net (code "116") (name "unconnected-(U1-PD7-Pad1)") (class "Default")
      (node (ref "U1") (pin "1") (pinfunction "PD7_1") (pintype "passive"))
    )
    (net (code "117") (name "unconnected-(U2-EN_BUCK-Pad55)") (class "Default")
      (node (ref "U2") (pin "55") (pinfunction "EN_BUCK_55") (pintype "passive+no_connect"))
    )
    (net (code "118") (name "unconnected-(U2-PWRGD-Pad4)") (class "Default")
      (node (ref "U2") (pin "4") (pinfunction "PWRGD_4") (pintype "passive+no_connect"))
    )
    (net (code "119") (name "unconnected-(U2-SS_TR-Pad56)") (class "Default")
      (node (ref "U2") (pin "56") (pinfunction "SS_TR_56") (pintype "passive+no_connect"))
    )
    (net (code "120") (name "unconnected-(U3-NC-Pad4)") (class "Default")
      (node (ref "U3") (pin "4") (pinfunction "NC_4") (pintype "passive+no_connect"))
    )
    (net (code "121") (name "unconnected-(U4-A-Pad7)") (class "Default")
      (node (ref "U4") (pin "7") (pinfunction "A_7") (pintype "passive+no_connect"))
    )
    (net (code "122") (name "unconnected-(U4-B-Pad6)") (class "Default")
      (node (ref "U4") (pin "6") (pinfunction "B_6") (pintype "passive+no_connect"))
    )
    (net (code "123") (name "unconnected-(U4-I{slash}PWM-Pad14)") (class "Default")
      (node (ref "U4") (pin "14") (pinfunction "I/PWM_14") (pintype "passive+no_connect"))
    )
    (net (code "124") (name "unconnected-(U4-U-Pad10)") (class "Default")
      (node (ref "U4") (pin "10") (pinfunction "U_10") (pintype "passive+no_connect"))
    )
    (net (code "125") (name "unconnected-(U4-V-Pad9)") (class "Default")
      (node (ref "U4") (pin "9") (pinfunction "V_9") (pintype "passive+no_connect"))
    )
    (net (code "126") (name "unconnected-(U4-W{slash}PWM-Pad8)") (class "Default")
      (node (ref "U4") (pin "8") (pinfunction "W/PWM_8") (pintype "passive+no_connect"))
    )
  )
)
